# Connectors.net
KiCad netlist of a schematic drawn in Altium Designer
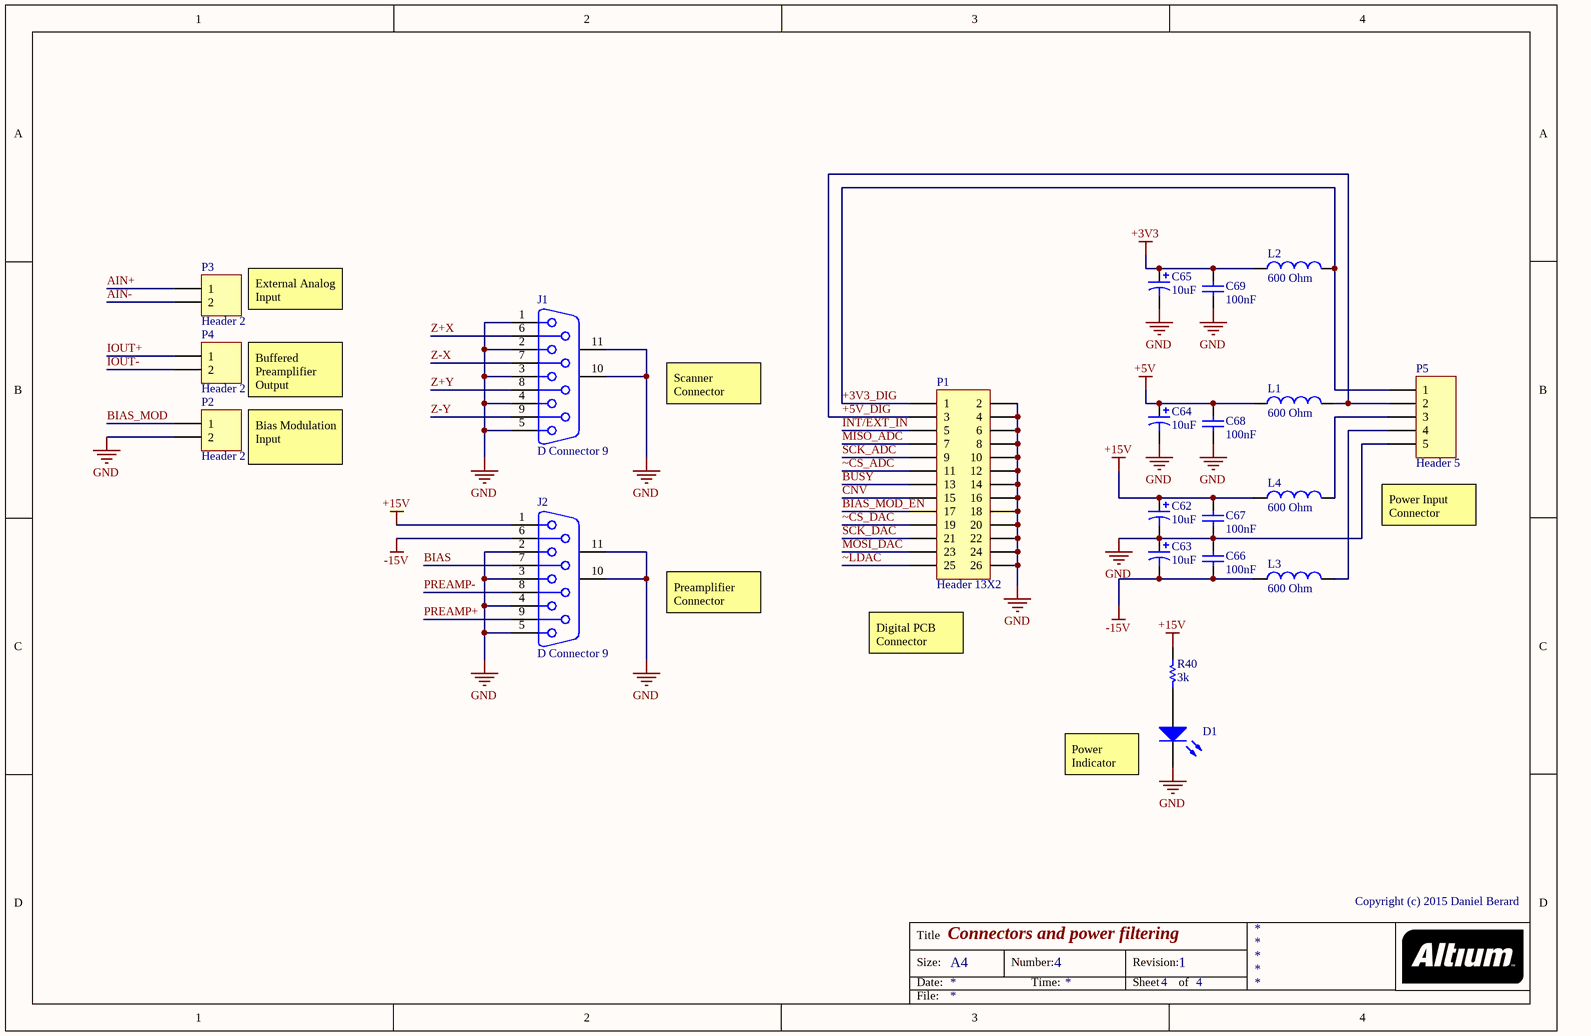
[diagram p0: Connectors.SchDoc]

(export (version "E")
  (design (tool "Eeschema 10.0.6"))
  (components
    (comp (ref "C62")
      (value "10uF")
      (footprint "3528")
      (description "Polarized Capacitor (Radial)")
      (fields (field (name "PUBLISHER") "Altium Limited"))
      (libsource (lib "Miscellaneous Devices") (part "Cap Pol1"))
    )
    (comp (ref "C63")
      (value "10uF")
      (footprint "3528")
      (description "Polarized Capacitor (Radial)")
      (fields (field (name "PUBLISHER") "Altium Limited"))
      (libsource (lib "Miscellaneous Devices") (part "Cap Pol1"))
    )
    (comp (ref "C64")
      (value "10uF")
      (footprint "6-0805_N")
      (description "Polarized Capacitor (Radial)")
      (fields (field (name "PUBLISHER") "Altium Limited"))
      (libsource (lib "Miscellaneous Devices") (part "Cap Pol1"))
    )
    (comp (ref "C65")
      (value "10uF")
      (footprint "6-0805_N")
      (description "Polarized Capacitor (Radial)")
      (fields (field (name "PUBLISHER") "Altium Limited"))
      (libsource (lib "Miscellaneous Devices") (part "Cap Pol1"))
    )
    (comp (ref "C66")
      (value "100nF")
      (footprint "6-0805_N")
      (description "Capacitor")
      (fields (field (name "PUBLISHER") "Altium Limited"))
      (libsource (lib "Miscellaneous Devices") (part "Cap"))
    )
    (comp (ref "C67")
      (value "100nF")
      (footprint "6-0805_N")
      (description "Capacitor")
      (fields (field (name "PUBLISHER") "Altium Limited"))
      (libsource (lib "Miscellaneous Devices") (part "Cap"))
    )
    (comp (ref "C68")
      (value "100nF")
      (footprint "6-0805_N")
      (description "Capacitor")
      (fields (field (name "PUBLISHER") "Altium Limited"))
      (libsource (lib "Miscellaneous Devices") (part "Cap"))
    )
    (comp (ref "C69")
      (value "100nF")
      (footprint "6-0805_N")
      (description "Capacitor")
      (fields (field (name "PUBLISHER") "Altium Limited"))
      (libsource (lib "Miscellaneous Devices") (part "Cap"))
    )
    (comp (ref "D1")
      (value "~")
      (footprint "6-0805_N")
      (description "Typical INFRARED GaAs LED")
      (fields (field (name "PUBLISHER") "Altium Limited"))
      (libsource (lib "Miscellaneous Devices") (part "LED0"))
    )
    (comp (ref "J1")
      (value "D Connector 9")
      (footprint "DSUB1.385-2H9")
      (description "Receptacle Assembly, 9 Position, Right Angle")
      (fields (field (name "PUBLISHER") "Altium Limited"))
      (libsource (lib "Miscellaneous Connectors") (part "D Connector 9"))
    )
    (comp (ref "J2")
      (value "D Connector 9")
      (footprint "DSUB1.385-2H9")
      (description "Receptacle Assembly, 9 Position, Right Angle")
      (fields (field (name "PUBLISHER") "Altium Limited"))
      (libsource (lib "Miscellaneous Connectors") (part "D Connector 9"))
    )
    (comp (ref "L1")
      (value "600 Ohm")
      (footprint "6-0805_N")
      (description "Inductor")
      (fields (field (name "PUBLISHER") "Altium Limited"))
      (libsource (lib "Miscellaneous Devices") (part "Inductor"))
    )
    (comp (ref "L2")
      (value "600 Ohm")
      (footprint "6-0805_N")
      (description "Inductor")
      (fields (field (name "PUBLISHER") "Altium Limited"))
      (libsource (lib "Miscellaneous Devices") (part "Inductor"))
    )
    (comp (ref "L3")
      (value "600 Ohm")
      (footprint "6-0805_N")
      (description "Inductor")
      (fields (field (name "PUBLISHER") "Altium Limited"))
      (libsource (lib "Miscellaneous Devices") (part "Inductor"))
    )
    (comp (ref "L4")
      (value "600 Ohm")
      (footprint "6-0805_N")
      (description "Inductor")
      (fields (field (name "PUBLISHER") "Altium Limited"))
      (libsource (lib "Miscellaneous Devices") (part "Inductor"))
    )
    (comp (ref "P1")
      (value "Header 13X2")
      (footprint "HDR2X13")
      (description "Header, 13-Pin, Dual row")
      (fields (field (name "PUBLISHER") "Altium Limited"))
      (libsource (lib "Miscellaneous Connectors") (part "Header 13X2"))
    )
    (comp (ref "P2")
      (value "Header 2")
      (footprint "HDR1X2")
      (description "Header, 2-Pin")
      (fields (field (name "PUBLISHER") "Altium Limited"))
      (libsource (lib "Miscellaneous Connectors") (part "Header 2"))
    )
    (comp (ref "P3")
      (value "Header 2")
      (footprint "HDR1X2")
      (description "Header, 2-Pin")
      (fields (field (name "PUBLISHER") "Altium Limited"))
      (libsource (lib "Miscellaneous Connectors") (part "Header 2"))
    )
    (comp (ref "P4")
      (value "Header 2")
      (footprint "HDR1X2")
      (description "Header, 2-Pin")
      (fields (field (name "PUBLISHER") "Altium Limited"))
      (libsource (lib "Miscellaneous Connectors") (part "Header 2"))
    )
    (comp (ref "P5")
      (value "Header 5")
      (footprint "HDR1X5")
      (description "Header, 5-Pin")
      (fields (field (name "PUBLISHER") "Altium Limited"))
      (libsource (lib "Miscellaneous Connectors") (part "Header 5"))
    )
    (comp (ref "R40")
      (value "3k")
      (footprint "6-0805_N")
      (description "Resistor")
      (fields (field (name "PUBLISHER") "Altium Limited"))
      (libsource (lib "Miscellaneous Devices") (part "Res1"))
    )
  )
  (nets
    (net (code "1") (name "+3V3") (class "Default")
      (node (ref "C65") (pin "1") (pinfunction "1_1") (pintype "passive"))
      (node (ref "C69") (pin "1") (pinfunction "1_1") (pintype "passive"))
      (node (ref "L2") (pin "1") (pinfunction "1_1") (pintype "passive"))
    )
    (net (code "2") (name "+5V") (class "Default")
      (node (ref "C64") (pin "1") (pinfunction "1_1") (pintype "passive"))
      (node (ref "C68") (pin "1") (pinfunction "1_1") (pintype "passive"))
      (node (ref "L1") (pin "1") (pinfunction "1_1") (pintype "passive"))
    )
    (net (code "3") (name "+15V") (class "Default")
      (node (ref "C62") (pin "1") (pinfunction "1_1") (pintype "passive"))
      (node (ref "C67") (pin "1") (pinfunction "1_1") (pintype "passive"))
      (node (ref "J2") (pin "1") (pinfunction "1_1") (pintype "passive"))
      (node (ref "L4") (pin "1") (pinfunction "1_1") (pintype "passive"))
      (node (ref "R40") (pin "2") (pinfunction "2_2") (pintype "passive"))
    )
    (net (code "4") (name "-15V") (class "Default")
      (node (ref "C63") (pin "2") (pinfunction "2_2") (pintype "passive"))
      (node (ref "C66") (pin "2") (pinfunction "2_2") (pintype "passive"))
      (node (ref "J2") (pin "6") (pinfunction "6_6") (pintype "passive"))
      (node (ref "L3") (pin "1") (pinfunction "1_1") (pintype "passive"))
    )
    (net (code "5") (name "/+3V3_DIG") (class "Default")
      (node (ref "L2") (pin "2") (pinfunction "2_2") (pintype "passive"))
      (node (ref "P1") (pin "1") (pinfunction "1_1") (pintype "passive"))
      (node (ref "P5") (pin "1") (pinfunction "1_1") (pintype "passive"))
    )
    (net (code "6") (name "/+5V_DIG") (class "Default")
      (node (ref "L1") (pin "2") (pinfunction "2_2") (pintype "passive"))
      (node (ref "P1") (pin "3") (pinfunction "3_3") (pintype "passive"))
      (node (ref "P5") (pin "2") (pinfunction "2_2") (pintype "passive"))
    )
    (net (code "7") (name "/AIN+") (class "Default")
      (node (ref "P3") (pin "1") (pinfunction "1_1") (pintype "passive"))
    )
    (net (code "8") (name "/AIN-") (class "Default")
      (node (ref "P3") (pin "2") (pinfunction "2_2") (pintype "passive"))
    )
    (net (code "9") (name "/BIAS") (class "Default")
      (node (ref "J2") (pin "7") (pinfunction "7_7") (pintype "passive"))
    )
    (net (code "10") (name "/BIAS_MOD") (class "Default")
      (node (ref "P2") (pin "1") (pinfunction "1_1") (pintype "passive"))
    )
    (net (code "11") (name "/BIAS_MOD_EN") (class "Default")
      (node (ref "P1") (pin "17") (pinfunction "17_17") (pintype "passive"))
    )
    (net (code "12") (name "/BUSY") (class "Default")
      (node (ref "P1") (pin "13") (pinfunction "13_13") (pintype "passive"))
    )
    (net (code "13") (name "/CNV") (class "Default")
      (node (ref "P1") (pin "15") (pinfunction "15_15") (pintype "passive"))
    )
    (net (code "14") (name "/INT{slash}EXT_IN") (class "Default")
      (node (ref "P1") (pin "5") (pinfunction "5_5") (pintype "passive"))
    )
    (net (code "15") (name "/IOUT+") (class "Default")
      (node (ref "P4") (pin "1") (pinfunction "1_1") (pintype "passive"))
    )
    (net (code "16") (name "/IOUT-") (class "Default")
      (node (ref "P4") (pin "2") (pinfunction "2_2") (pintype "passive"))
    )
    (net (code "17") (name "/MISO_ADC") (class "Default")
      (node (ref "P1") (pin "7") (pinfunction "7_7") (pintype "passive"))
    )
    (net (code "18") (name "/MOSI_DAC") (class "Default")
      (node (ref "P1") (pin "23") (pinfunction "23_23") (pintype "passive"))
    )
    (net (code "19") (name "/PREAMP+") (class "Default")
      (node (ref "J2") (pin "9") (pinfunction "9_9") (pintype "passive"))
    )
    (net (code "20") (name "/PREAMP-") (class "Default")
      (node (ref "J2") (pin "8") (pinfunction "8_8") (pintype "passive"))
    )
    (net (code "21") (name "/SCK_ADC") (class "Default")
      (node (ref "P1") (pin "9") (pinfunction "9_9") (pintype "passive"))
    )
    (net (code "22") (name "/SCK_DAC") (class "Default")
      (node (ref "P1") (pin "21") (pinfunction "21_21") (pintype "passive"))
    )
    (net (code "23") (name "/Z+X") (class "Default")
      (node (ref "J1") (pin "6") (pinfunction "6_6") (pintype "passive"))
    )
    (net (code "24") (name "/Z+Y") (class "Default")
      (node (ref "J1") (pin "8") (pinfunction "8_8") (pintype "passive"))
    )
    (net (code "25") (name "/Z-X") (class "Default")
      (node (ref "J1") (pin "7") (pinfunction "7_7") (pintype "passive"))
    )
    (net (code "26") (name "/Z-Y") (class "Default")
      (node (ref "J1") (pin "9") (pinfunction "9_9") (pintype "passive"))
    )
    (net (code "27") (name "/~CS_ADC") (class "Default")
      (node (ref "P1") (pin "11") (pinfunction "11_11") (pintype "passive"))
    )
    (net (code "28") (name "/~CS_DAC") (class "Default")
      (node (ref "P1") (pin "19") (pinfunction "19_19") (pintype "passive"))
    )
    (net (code "29") (name "/~LDAC") (class "Default")
      (node (ref "P1") (pin "25") (pinfunction "25_25") (pintype "passive"))
    )
    (net (code "30") (name "GND") (class "Default")
      (node (ref "C62") (pin "2") (pinfunction "2_2") (pintype "passive"))
      (node (ref "C63") (pin "1") (pinfunction "1_1") (pintype "passive"))
      (node (ref "C64") (pin "2") (pinfunction "2_2") (pintype "passive"))
      (node (ref "C65") (pin "2") (pinfunction "2_2") (pintype "passive"))
      (node (ref "C66") (pin "1") (pinfunction "1_1") (pintype "passive"))
      (node (ref "C67") (pin "2") (pinfunction "2_2") (pintype "passive"))
      (node (ref "C68") (pin "2") (pinfunction "2_2") (pintype "passive"))
      (node (ref "C69") (pin "2") (pinfunction "2_2") (pintype "passive"))
      (node (ref "D1") (pin "2") (pinfunction "K_2") (pintype "passive"))
      (node (ref "J1") (pin "1") (pinfunction "1_1") (pintype "passive"))
      (node (ref "J1") (pin "10") (pinfunction "MH1_10") (pintype "passive"))
      (node (ref "J1") (pin "11") (pinfunction "MH2_11") (pintype "passive"))
      (node (ref "J1") (pin "2") (pinfunction "2_2") (pintype "passive"))
      (node (ref "J1") (pin "3") (pinfunction "3_3") (pintype "passive"))
      (node (ref "J1") (pin "4") (pinfunction "4_4") (pintype "passive"))
      (node (ref "J1") (pin "5") (pinfunction "5_5") (pintype "passive"))
      (node (ref "J2") (pin "10") (pinfunction "MH1_10") (pintype "passive"))
      (node (ref "J2") (pin "11") (pinfunction "MH2_11") (pintype "passive"))
      (node (ref "J2") (pin "2") (pinfunction "2_2") (pintype "passive"))
      (node (ref "J2") (pin "3") (pinfunction "3_3") (pintype "passive"))
      (node (ref "J2") (pin "4") (pinfunction "4_4") (pintype "passive"))
      (node (ref "J2") (pin "5") (pinfunction "5_5") (pintype "passive"))
      (node (ref "P1") (pin "10") (pinfunction "10_10") (pintype "passive"))
      (node (ref "P1") (pin "12") (pinfunction "12_12") (pintype "passive"))
      (node (ref "P1") (pin "14") (pinfunction "14_14") (pintype "passive"))
      (node (ref "P1") (pin "16") (pinfunction "16_16") (pintype "passive"))
      (node (ref "P1") (pin "18") (pinfunction "18_18") (pintype "passive"))
      (node (ref "P1") (pin "2") (pinfunction "2_2") (pintype "passive"))
      (node (ref "P1") (pin "20") (pinfunction "20_20") (pintype "passive"))
      (node (ref "P1") (pin "22") (pinfunction "22_22") (pintype "passive"))
      (node (ref "P1") (pin "24") (pinfunction "24_24") (pintype "passive"))
      (node (ref "P1") (pin "26") (pinfunction "26_26") (pintype "passive"))
      (node (ref "P1") (pin "4") (pinfunction "4_4") (pintype "passive"))
      (node (ref "P1") (pin "6") (pinfunction "6_6") (pintype "passive"))
      (node (ref "P1") (pin "8") (pinfunction "8_8") (pintype "passive"))
      (node (ref "P2") (pin "2") (pinfunction "2_2") (pintype "passive"))
      (node (ref "P5") (pin "5") (pinfunction "5_5") (pintype "passive"))
    )
    (net (code "31") (name "Net-(D1-A)") (class "Default")
      (node (ref "D1") (pin "1") (pinfunction "A_1") (pintype "passive"))
      (node (ref "R40") (pin "1") (pinfunction "1_1") (pintype "passive"))
    )
    (net (code "32") (name "Net-(L3-Pad2)") (class "Default")
      (node (ref "L3") (pin "2") (pinfunction "2_2") (pintype "passive"))
      (node (ref "P5") (pin "4") (pinfunction "4_4") (pintype "passive"))
    )
    (net (code "33") (name "Net-(L4-Pad2)") (class "Default")
      (node (ref "L4") (pin "2") (pinfunction "2_2") (pintype "passive"))
      (node (ref "P5") (pin "3") (pinfunction "3_3") (pintype "passive"))
    )
  )
)
